# WIRE_CONVERTER.net
KiCad netlist of a schematic drawn in Altium Designer
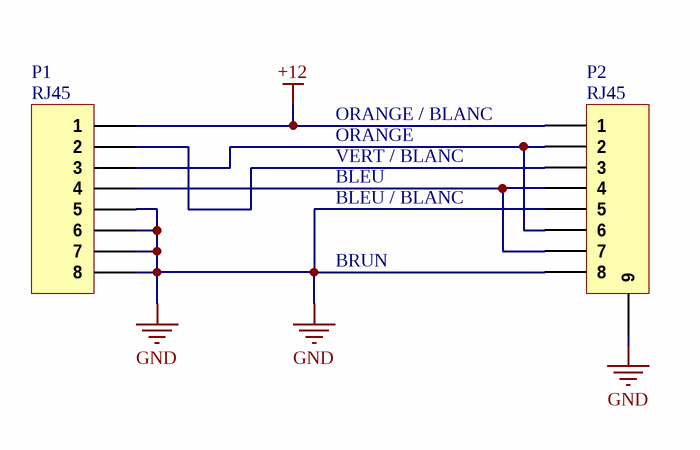
[diagram p0: WIRE CONVERTER.SchDoc]

(export (version "E")
  (design (tool "Eeschema 10.0.6"))
  (components
    (comp (ref "P1")
      (value "RJ45")
      (footprint "SYLANN:Amphenol-RJ45_8")
      (description "Header, 8-Pin")
      (fields (field (name "MANUFACTURER") "MOLEX") (field (name "MANUFACTURER PART NUMBER") "85502-5008"))
      (libsource (lib "Miscellaneous Connectors") (part "Header 8"))
    )
    (comp (ref "P2")
      (value "RJ45")
      (footprint "AMPHENOL-RJ45_8")
      (description "Header, 8-Pin")
      (fields
        (field (name "MANUFACTURER") "MOLEX")
        (field (name "MANUFACTURER PART NUMBER") "85513-5013")
        (field (name "APPROVAL CATEGORY") "UL 94V-0")
        (field (name "LONGUEUR/HAUTEUR") "13")
      )
      (libsource (lib "MAIN BOARD CERES") (part "Header 8"))
    )
  )
  (nets
    (net (code "1") (name "+12") (class "Default")
      (node (ref "P1") (pin "1") (pinfunction "1_1") (pintype "passive"))
      (node (ref "P2") (pin "1") (pinfunction "1_1") (pintype "passive"))
    )
    (net (code "2") (name "GND") (class "Default")
      (node (ref "P1") (pin "5") (pinfunction "5_5") (pintype "passive"))
      (node (ref "P1") (pin "6") (pinfunction "6_6") (pintype "passive"))
      (node (ref "P1") (pin "7") (pinfunction "7_7") (pintype "passive"))
      (node (ref "P1") (pin "8") (pinfunction "8_8") (pintype "passive"))
      (node (ref "P2") (pin "5") (pinfunction "5_5") (pintype "passive"))
      (node (ref "P2") (pin "8") (pinfunction "8_8") (pintype "passive"))
      (node (ref "P2") (pin "9") (pinfunction "9_9") (pintype "passive"))
    )
    (net (code "3") (name "Net-(P1-Pad2)") (class "Default")
      (node (ref "P1") (pin "2") (pinfunction "2_2") (pintype "passive"))
      (node (ref "P2") (pin "3") (pinfunction "3_3") (pintype "passive"))
    )
    (net (code "4") (name "Net-(P1-Pad3)") (class "Default")
      (node (ref "P1") (pin "3") (pinfunction "3_3") (pintype "passive"))
      (node (ref "P2") (pin "2") (pinfunction "2_2") (pintype "passive"))
      (node (ref "P2") (pin "6") (pinfunction "6_6") (pintype "passive"))
    )
    (net (code "5") (name "Net-(P1-Pad4)") (class "Default")
      (node (ref "P1") (pin "4") (pinfunction "4_4") (pintype "passive"))
      (node (ref "P2") (pin "4") (pinfunction "4_4") (pintype "passive"))
      (node (ref "P2") (pin "7") (pinfunction "7_7") (pintype "passive"))
    )
  )
)
